# VOLTAGE_SOURCE.net
KiCad netlist of a schematic drawn in Altium Designer
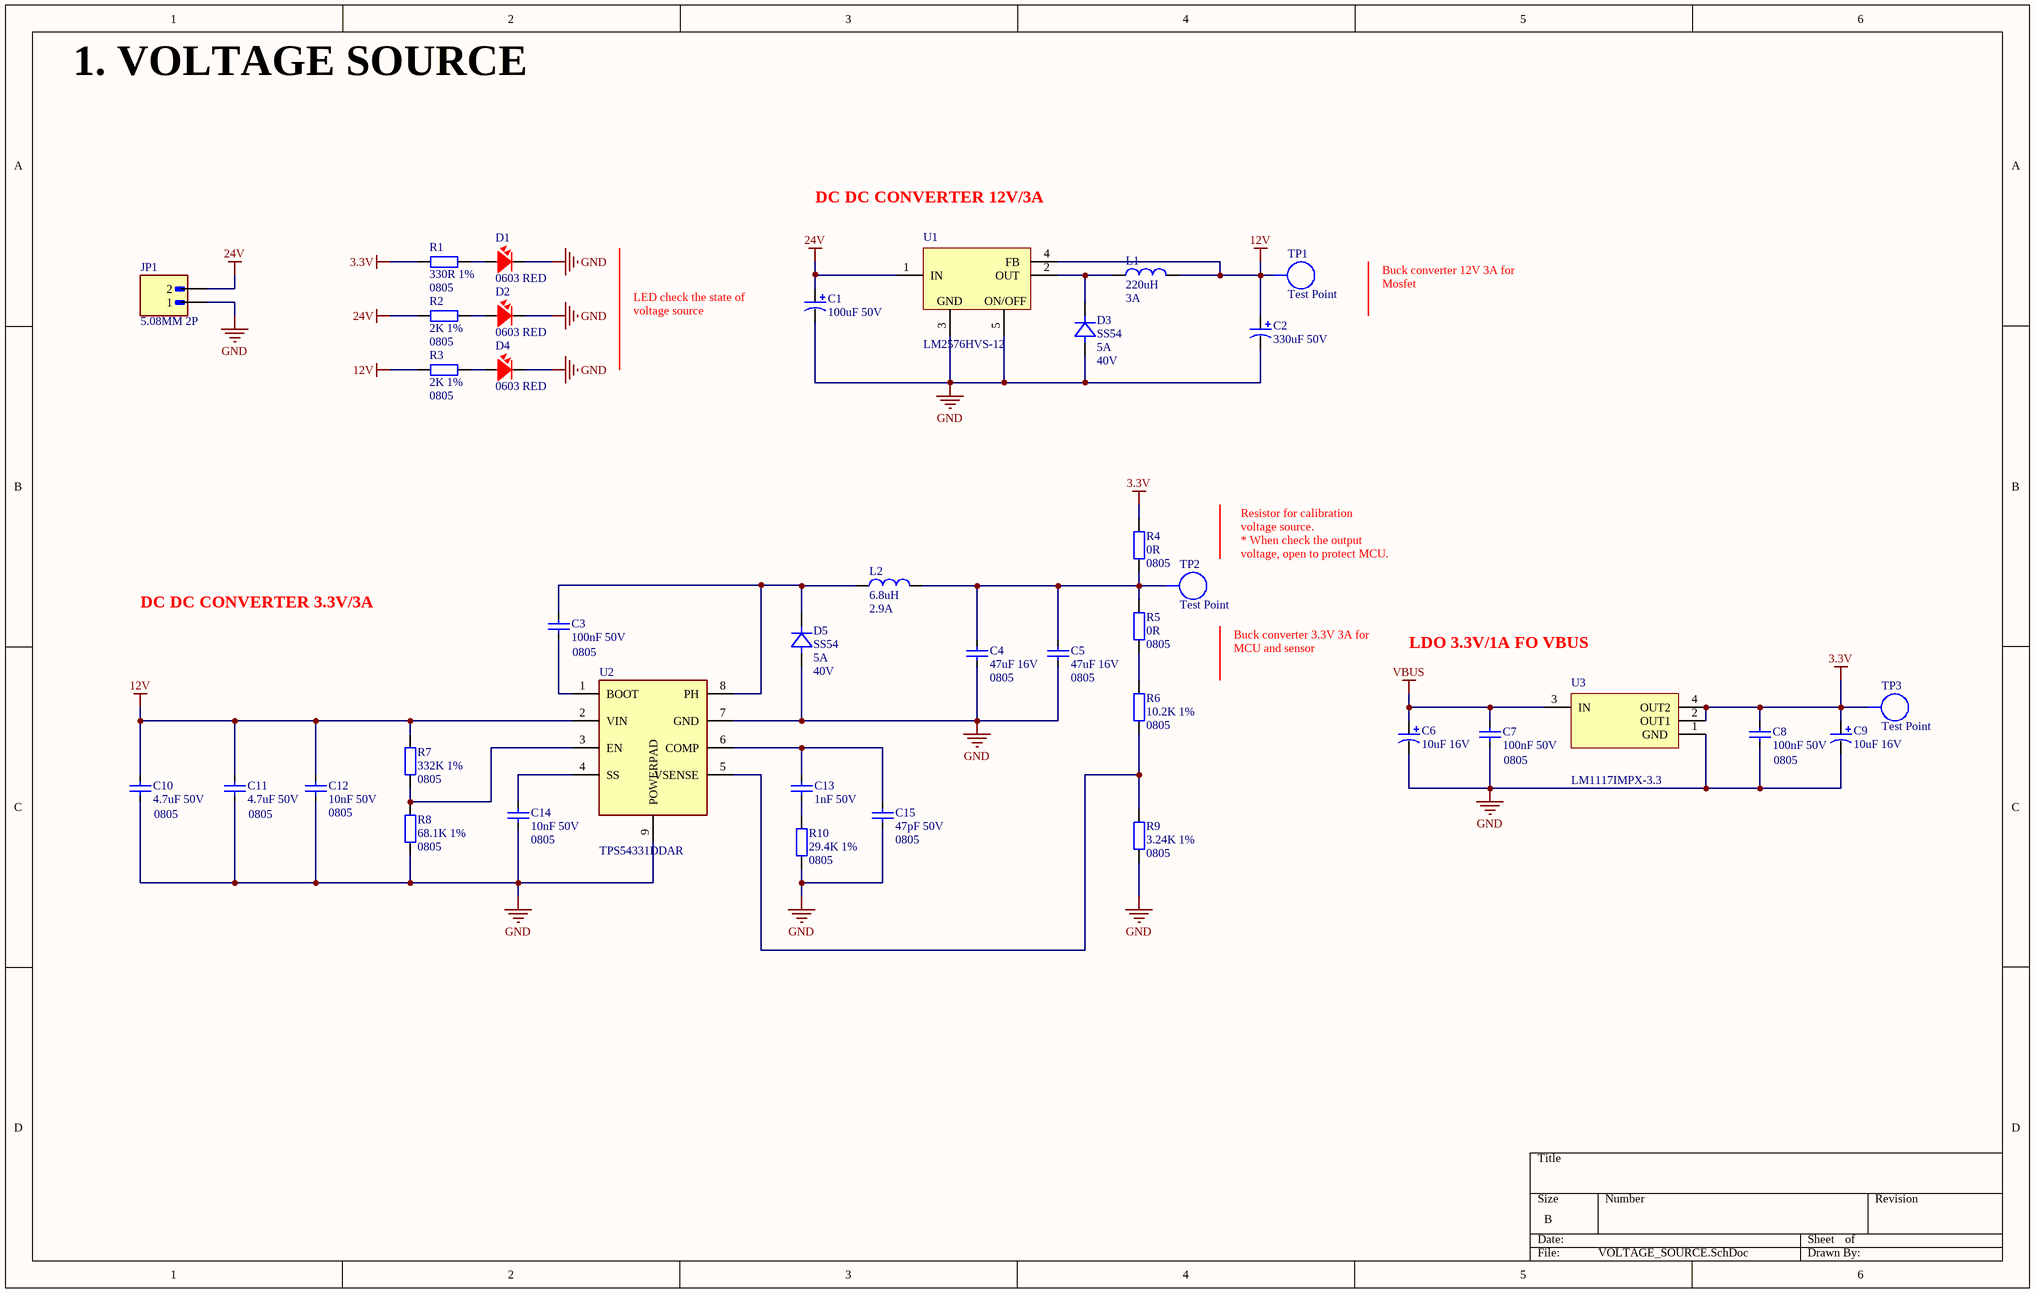
[diagram p0: VOLTAGE_SOURCE.SchDoc]

(export (version "E")
  (design (tool "Eeschema 10.0.6"))
  (components
    (comp (ref "C1")
      (value "100uF 50V")
      (footprint "CAP-ALU-SMD-F-NEW")
      (description "100uF 50V 140mA@120Hz ±20% SMD,D8xL10mm Aluminum Electrolytic Capacitors - SMD ROHS")
      (fields
        (field (name "MANUFACTURER") "Nichicon")
        (field (name "MANUFACTURE PART NUMBER") "UWT1H101MNL1GS")
      )
      (libsource (lib "Capacitors") (part "C_ALU_100uF_50V_F"))
    )
    (comp (ref "C2")
      (value "330uF 50V")
      (footprint "CAP-ALU-SMD-G-NEW")
      (description "330uF 50V 170mA@120Hz ±20% SMD,D10xL10.2mm Aluminum Electrolytic Capacitors - SMD ROHS")
      (fields
        (field (name "MANUFACTURER") "KNSCHA")
        (field (name "MANUFACTURE PART NUMBER") "RVT330UF50V167RV085")
      )
      (libsource (lib "Capacitors") (part "C_ALU_330uF_50V_G"))
    )
    (comp (ref "C3")
      (value "100nF 50V")
      (footprint "CAP_SMD_0805_NEW")
      (description "0.1 µF ±10% 50V Ceramic Capacitor X7R 0805 (2012 Metric)")
      (fields
        (field (name "MANUFACTURER") "YAGEO")
        (field (name "MANUFACTURE PART NUMBER") "CC0805KRX7R9BB104")
        (field (name "SIZE") "0805")
      )
      (libsource (lib "Capacitors") (part "C0805_MLCC_100nF_50V"))
    )
    (comp (ref "C4")
      (value "47uF 16V")
      (footprint "CAP_SMD_0805_NEW")
      (description "47 µF ±10% 16V Ceramic Capacitor X5R 1210 (3225 Metric)")
      (fields
        (field (name "MANUFACTURER") "Samsung Electro-Mechanics")
        (field (name "MANUFACTURE PART NUMBER") "CL32A476KOJNNNE")
        (field (name "SIZE") "0805")
      )
      (libsource (lib "Capacitors") (part "C0805_MLCC_47uF_16V"))
    )
    (comp (ref "C5")
      (value "47uF 16V")
      (footprint "CAP_SMD_0805_NEW")
      (description "47 µF ±10% 16V Ceramic Capacitor X5R 1210 (3225 Metric)")
      (fields
        (field (name "MANUFACTURER") "Samsung Electro-Mechanics")
        (field (name "MANUFACTURE PART NUMBER") "CL32A476KOJNNNE")
        (field (name "SIZE") "0805")
      )
      (libsource (lib "Capacitors") (part "C0805_MLCC_47uF_16V"))
    )
    (comp (ref "C6")
      (value "10uF 16V")
      (footprint "CAP-ALU-SMD-B -NEW")
      (description "10uF 16V 14mA@120Hz ±20% SMD,D4xL5.4mm Aluminum Electrolytic Capacitors - SMD ROHS")
      (fields (field (name "MANUFACTURER") "KNSCHA") (field (name "MANUFACTURE PART NUMBER") "RST10UF16V013"))
      (libsource (lib "Capacitors") (part "C_ALU_10uF_16V_B"))
    )
    (comp (ref "C7")
      (value "100nF 50V")
      (footprint "CAP_SMD_0805_NEW")
      (description "0.1 µF ±10% 50V Ceramic Capacitor X7R 0805 (2012 Metric)")
      (fields
        (field (name "MANUFACTURER") "YAGEO")
        (field (name "MANUFACTURE PART NUMBER") "CC0805KRX7R9BB104")
        (field (name "SIZE") "0805")
      )
      (libsource (lib "Capacitors") (part "C0805_MLCC_100nF_50V"))
    )
    (comp (ref "C8")
      (value "100nF 50V")
      (footprint "CAP_SMD_0805_NEW")
      (description "0.1 µF ±10% 50V Ceramic Capacitor X7R 0805 (2012 Metric)")
      (fields
        (field (name "MANUFACTURER") "YAGEO")
        (field (name "MANUFACTURE PART NUMBER") "CC0805KRX7R9BB104")
        (field (name "SIZE") "0805")
      )
      (libsource (lib "Capacitors") (part "C0805_MLCC_100nF_50V"))
    )
    (comp (ref "C9")
      (value "10uF 16V")
      (footprint "CAP-ALU-SMD-B -NEW")
      (description "10uF 16V 14mA@120Hz ±20% SMD,D4xL5.4mm Aluminum Electrolytic Capacitors - SMD ROHS")
      (fields (field (name "MANUFACTURER") "KNSCHA") (field (name "MANUFACTURE PART NUMBER") "RST10UF16V013"))
      (libsource (lib "Capacitors") (part "C_ALU_10uF_16V_B"))
    )
    (comp (ref "C10")
      (value "4.7uF 50V")
      (footprint "CAP_SMD_0805_NEW")
      (description "4.7 µF ±10% 50V Ceramic Capacitor X5R 0805 (2012 Metric)")
      (fields
        (field (name "MANUFACTURER") "Samsung Electro-Mechanics")
        (field (name "MANUFACTURE PART NUMBER") "CL21A475KBQNNNE")
        (field (name "SIZE") "0805")
      )
      (libsource (lib "Capacitors") (part "C0805_MLCC_4.7uF_50V"))
    )
    (comp (ref "C11")
      (value "4.7uF 50V")
      (footprint "CAP_SMD_0805_NEW")
      (description "4.7 µF ±10% 50V Ceramic Capacitor X5R 0805 (2012 Metric)")
      (fields
        (field (name "MANUFACTURER") "Samsung Electro-Mechanics")
        (field (name "MANUFACTURE PART NUMBER") "CL21A475KBQNNNE")
        (field (name "SIZE") "0805")
      )
      (libsource (lib "Capacitors") (part "C0805_MLCC_4.7uF_50V"))
    )
    (comp (ref "C12")
      (value "10nF 50V")
      (footprint "CAP_SMD_0805_NEW")
      (description "10000 pF ±10% 50V Ceramic Capacitor X7R 0805 (2012 Metric)")
      (fields
        (field (name "MANUFACTURER") "Samsung Electro-Mechanics")
        (field (name "MANUFACTURE PART NUMBER") "CL21B103KBANNNC")
        (field (name "SIZE") "0805")
      )
      (libsource (lib "Capacitors") (part "C0805_MLCC_10nF_50V"))
    )
    (comp (ref "C13")
      (value "1nF 50V")
      (footprint "CAP_SMD_0805_NEW")
      (description "1000 pF ±5% 50V Ceramic Capacitor C0G, NP0 0805 (2012 Metric)")
      (fields
        (field (name "MANUFACTURER") "KEMET")
        (field (name "MANUFACTURE PART NUMBER") "C0805C102J5GAC7800")
      )
      (libsource (lib "Capacitors") (part "C0805_MLCC_1nF_50V"))
    )
    (comp (ref "C14")
      (value "10nF 50V")
      (footprint "CAP_SMD_0805_NEW")
      (description "10000 pF ±10% 50V Ceramic Capacitor X7R 0805 (2012 Metric)")
      (fields
        (field (name "MANUFACTURER") "Samsung Electro-Mechanics")
        (field (name "MANUFACTURE PART NUMBER") "CL21B103KBANNNC")
        (field (name "SIZE") "0805")
      )
      (libsource (lib "Capacitors") (part "C0805_MLCC_10nF_50V"))
    )
    (comp (ref "C15")
      (value "47pF 50V")
      (footprint "CAP_SMD_0805_NEW")
      (description "47 pF ±5% 50V Ceramic Capacitor C0G, NP0 0805 (2012 Metric)")
      (fields
        (field (name "MANUFACTURER") "YAGEO")
        (field (name "MANUFACTURE PART NUMBER") "CC0805JRNPO9BN470")
        (field (name "SIZE") "0805")
      )
      (libsource (lib "Capacitors") (part "C0805_MLCC_47pF_50V"))
    )
    (comp (ref "D1")
      (value "0603 RED")
      (footprint "LED-0603")
      (description "Red 625nm LED Indication - Discrete 2V 0603 (1608 Metric)")
      (fields
        (field (name "MANUFACTURER") "Würth Elektronik")
        (field (name "MANUFACTURE PART NUMBER") "150060RS75000")
      )
      (libsource (lib "LEDs") (part "LED_0603_RED"))
    )
    (comp (ref "D2")
      (value "0603 RED")
      (footprint "LED-0603")
      (description "Red 625nm LED Indication - Discrete 2V 0603 (1608 Metric)")
      (fields
        (field (name "MANUFACTURER") "Würth Elektronik")
        (field (name "MANUFACTURE PART NUMBER") "150060RS75000")
      )
      (libsource (lib "LEDs") (part "LED_0603_RED"))
    )
    (comp (ref "D3")
      (value "SS54")
      (footprint "SMA")
      (description "DIODE SCHOTTKY 40V 5A SMA")
      (fields
        (field (name "MANUFACTURER") "EVVO")
        (field (name "CURRENT") "5A")
        (field (name "DC VOLTAGE") "40V")
      )
      (libsource (lib "Diode") (part "SS54"))
    )
    (comp (ref "D4")
      (value "0603 RED")
      (footprint "LED-0603")
      (description "Red 625nm LED Indication - Discrete 2V 0603 (1608 Metric)")
      (fields
        (field (name "MANUFACTURER") "Würth Elektronik")
        (field (name "MANUFACTURE PART NUMBER") "150060RS75000")
      )
      (libsource (lib "LEDs") (part "LED_0603_RED"))
    )
    (comp (ref "D5")
      (value "SS54")
      (footprint "SMA")
      (description "DIODE SCHOTTKY 40V 5A SMA")
      (fields
        (field (name "MANUFACTURER") "EVVO")
        (field (name "CURRENT") "5A")
        (field (name "DC VOLTAGE") "40V")
      )
      (libsource (lib "Diode") (part "SS54"))
    )
    (comp (ref "JP1")
      (value "5.08MM 2P")
      (footprint "5.08MM 2P")
      (fields
        (field (name "MANUFACTURER") "Phoenix Contact")
        (field (name "MANUFACTURE PART NUMBER") "1759017")
      )
      (libsource (lib "Connectors") (part "TERMINAL_5.08MM_2P"))
    )
    (comp (ref "L1")
      (value "220uH 3A")
      (footprint "L_TOR_13x7")
      (fields (field (name "INDUCTOR") "220uH") (field (name "CURRENT") "3A"))
      (libsource (lib "Inductors") (part "L_220uH_3A_LM2576"))
    )
    (comp (ref "L2")
      (value "CD74R_6.8uH")
      (footprint "CD74R")
      (description "2.9A 6.8uH ±30% SMD,7.5x7.5mm Power Inductors ROHS")
      (fields
        (field (name "MANUFACTURER") "SHOU HAN")
        (field (name "MANUFACTURE PART NUMBER") "CYH74-6.8UH")
        (field (name "INDUCTOR") "6.8uH")
        (field (name "CURRENT") "2.9A")
      )
      (libsource (lib "Inductors") (part "CD74R_6.8uH"))
    )
    (comp (ref "R1")
      (value "330R 1%")
      (footprint "RES_SMD_0805")
      (description "330 Ohms ±1% 0.125W, 1/8W Chip Resistor 0805 (2012 Metric) Automotive AEC-Q200 Thick Film")
      (fields
        (field (name "MANUFACTURER") "Stackpole Electronics Inc")
        (field (name "MANUFACTURE PART NUMBER") "RMCF0805FT330R")
        (field (name "SIZE") "0805")
      )
      (libsource (lib "Resistors") (part "R0805_330R"))
    )
    (comp (ref "R2")
      (value "2K 1%")
      (footprint "RES_SMD_0805")
      (description "2 kOhms ±1% 0.125W, 1/8W Chip Resistor 0805 (2012 Metric) Automotive AEC-Q200 Thick Film")
      (fields
        (field (name "MANUFACTURER") "Panasonic Electronic Components")
        (field (name "MANUFACTURE PART NUMBER") "ERJ-6ENF2001V")
        (field (name "SIZE") "0805")
      )
      (libsource (lib "Resistors") (part "R0805_2K"))
    )
    (comp (ref "R3")
      (value "2K 1%")
      (footprint "RES_SMD_0805")
      (description "2 kOhms ±1% 0.125W, 1/8W Chip Resistor 0805 (2012 Metric) Automotive AEC-Q200 Thick Film")
      (fields
        (field (name "MANUFACTURER") "Panasonic Electronic Components")
        (field (name "MANUFACTURE PART NUMBER") "ERJ-6ENF2001V")
        (field (name "SIZE") "0805")
      )
      (libsource (lib "Resistors") (part "R0805_2K"))
    )
    (comp (ref "R4")
      (value "0R")
      (footprint "RES_SMD_0805")
      (description "0 Ohms Jumper Chip Resistor 0805 (2012 Metric) Automotive AEC-Q200 Thick Film")
      (fields
        (field (name "MANUFACTURER") "Vishay Dale")
        (field (name "MANUFACTURE PART NUMBER") "CRCW08050000Z0EA")
        (field (name "SIZE") "0805")
      )
      (libsource (lib "Resistors") (part "R0805_0R"))
    )
    (comp (ref "R5")
      (value "0R")
      (footprint "RES_SMD_0805")
      (description "0 Ohms Jumper Chip Resistor 0805 (2012 Metric) Automotive AEC-Q200 Thick Film")
      (fields
        (field (name "MANUFACTURER") "Vishay Dale")
        (field (name "MANUFACTURE PART NUMBER") "CRCW08050000Z0EA")
        (field (name "SIZE") "0805")
      )
      (libsource (lib "Resistors") (part "R0805_0R"))
    )
    (comp (ref "R6")
      (value "10.2K 1%")
      (footprint "RES_SMD_0805")
      (description "10.2 kOhms ±1% 0.125W, 1/8W Chip Resistor 0805 (2012 Metric) Moisture Resistant Thick Film")
      (fields
        (field (name "MANUFACTURER") "YAGEO")
        (field (name "MANUFACTURE PART NUMBER") "RC0805FR-0710K2L")
        (field (name "SIZE") "0805")
      )
      (libsource (lib "Resistors") (part "R0805_10.2K"))
    )
    (comp (ref "R7")
      (value "332K 1%")
      (footprint "RES_SMD_0805")
      (description "332 kOhms ±1% 0.125W, 1/8W Chip Resistor 0805 (2012 Metric) Moisture Resistant Thick Film")
      (fields
        (field (name "MANUFACTURER") "YAGEO")
        (field (name "MANUFACTURE PART NUMBER") "RC0805FR-07332KL")
        (field (name "SIZE") "0805")
      )
      (libsource (lib "Resistors") (part "R0805_332K"))
    )
    (comp (ref "R8")
      (value "68.1K 1%")
      (footprint "RES_SMD_0805")
      (description "68.1 kOhms ±1% 0.125W, 1/8W Chip Resistor 0805 (2012 Metric) Moisture Resistant Thick Film")
      (fields
        (field (name "MANUFACTURER") "YAGEO")
        (field (name "MANUFACTURE PART NUMBER") "RC0805FR-0768K1L")
        (field (name "SIZE") "0805")
      )
      (libsource (lib "Resistors") (part "R0805_68.1K"))
    )
    (comp (ref "R9")
      (value "3.24K 1%")
      (footprint "RES_SMD_0805")
      (description "3.24 kOhms ±1% 0.125W, 1/8W Chip Resistor 0805 (2012 Metric) Moisture Resistant Thick Film")
      (fields
        (field (name "MANUFACTURER") "YAGEO")
        (field (name "MANUFACTURE PART NUMBER") "RC0805FR-073K24L")
        (field (name "SIZE") "0805")
      )
      (libsource (lib "Resistors") (part "R0805_3.24K"))
    )
    (comp (ref "R10")
      (value "29.4K 1%")
      (footprint "RES_SMD_0805")
      (description "29.4 kOhms ±1% 0.125W, 1/8W Chip Resistor 0805 (2012 Metric) Moisture Resistant Thick Film")
      (fields
        (field (name "MANUFACTURER") "YAGEO")
        (field (name "MANUFACTURE PART NUMBER") "RC0805FR-0729K4L")
        (field (name "SIZE") "0805")
      )
      (libsource (lib "Resistors") (part "R0805_29.4K"))
    )
    (comp (ref "TP1")
      (value "Test Point")
      (footprint "TEST_POINT")
      (libsource (lib "Connectors") (part "TEST_POINT"))
    )
    (comp (ref "TP2")
      (value "Test Point")
      (footprint "TEST_POINT")
      (libsource (lib "Connectors") (part "TEST_POINT"))
    )
    (comp (ref "TP3")
      (value "Test Point")
      (footprint "TEST_POINT")
      (libsource (lib "Connectors") (part "TEST_POINT"))
    )
    (comp (ref "U1")
      (value "LM2576HVS-12")
      (footprint "IC_LM2596SX-12/NOPB")
      (fields (field (name "MANUFACTURER") "Texas Instruments"))
      (libsource (lib "Voltage_Regulators") (part "LM2576HVS-12"))
    )
    (comp (ref "U2")
      (value "TPS54331DDAR")
      (footprint "TPS54531DDAR")
      (fields (field (name "MANUFACTURER") "Texas Instruments"))
      (libsource (lib "Voltage_Regulators") (part "TPS54331DDAR"))
    )
    (comp (ref "U3")
      (value "LM1117IMPX-3.3")
      (footprint "SOT-223-4")
      (description "Linear Voltage Regulator IC Positive Fixed 1 Output 800mA SOT-223-4")
      (fields
        (field (name "MANUFACTURER") "Texas Instruments")
        (field (name "MANUFACTURE PART NUMBER") "LM1117IMPX-3.3/NOPB")
      )
      (libsource (lib "Voltage_Regulators") (part "LM1117IMPX-3.3/NOPB"))
    )
  )
  (nets
    (net (code "1") (name "3.3V") (class "Default")
      (node (ref "C8") (pin "2") (pinfunction "2_2") (pintype "passive"))
      (node (ref "C9") (pin "1") (pinfunction "1_1") (pintype "passive"))
      (node (ref "R1") (pin "1") (pinfunction "1_1") (pintype "passive"))
      (node (ref "R4") (pin "2") (pinfunction "2_2") (pintype "passive"))
      (node (ref "TP3") (pin "1") (pinfunction "1_1") (pintype "passive"))
      (node (ref "U3") (pin "2") (pinfunction "OUT1_2") (pintype "passive"))
      (node (ref "U3") (pin "4") (pinfunction "OUT2_4") (pintype "passive"))
    )
    (net (code "2") (name "12V") (class "Default")
      (node (ref "C10") (pin "2") (pinfunction "2_2") (pintype "passive"))
      (node (ref "C11") (pin "2") (pinfunction "2_2") (pintype "passive"))
      (node (ref "C12") (pin "2") (pinfunction "2_2") (pintype "passive"))
      (node (ref "C2") (pin "1") (pinfunction "1_1") (pintype "passive"))
      (node (ref "L1") (pin "2") (pinfunction "2_2") (pintype "passive"))
      (node (ref "R3") (pin "2") (pinfunction "2_2") (pintype "passive"))
      (node (ref "R7") (pin "2") (pinfunction "2_2") (pintype "passive"))
      (node (ref "TP1") (pin "1") (pinfunction "1_1") (pintype "passive"))
      (node (ref "U1") (pin "4") (pinfunction "FB_4") (pintype "passive"))
      (node (ref "U2") (pin "2") (pinfunction "VIN_2") (pintype "passive"))
    )
    (net (code "3") (name "24V") (class "Default")
      (node (ref "C1") (pin "1") (pinfunction "1_1") (pintype "passive"))
      (node (ref "JP1") (pin "2") (pinfunction "2_2") (pintype "passive"))
      (node (ref "R2") (pin "2") (pinfunction "2_2") (pintype "passive"))
      (node (ref "U1") (pin "1") (pinfunction "IN_1") (pintype "passive"))
    )
    (net (code "4") (name "GND") (class "Default")
      (node (ref "C1") (pin "2") (pinfunction "2_2") (pintype "passive"))
      (node (ref "C10") (pin "1") (pinfunction "1_1") (pintype "passive"))
      (node (ref "C11") (pin "1") (pinfunction "1_1") (pintype "passive"))
      (node (ref "C12") (pin "1") (pinfunction "1_1") (pintype "passive"))
      (node (ref "C14") (pin "1") (pinfunction "1_1") (pintype "passive"))
      (node (ref "C15") (pin "1") (pinfunction "1_1") (pintype "passive"))
      (node (ref "C2") (pin "2") (pinfunction "2_2") (pintype "passive"))
      (node (ref "C4") (pin "1") (pinfunction "1_1") (pintype "passive"))
      (node (ref "C5") (pin "1") (pinfunction "1_1") (pintype "passive"))
      (node (ref "C6") (pin "2") (pinfunction "2_2") (pintype "passive"))
      (node (ref "C7") (pin "1") (pinfunction "1_1") (pintype "passive"))
      (node (ref "C8") (pin "1") (pinfunction "1_1") (pintype "passive"))
      (node (ref "C9") (pin "2") (pinfunction "2_2") (pintype "passive"))
      (node (ref "D1") (pin "2") (pinfunction "2_2") (pintype "passive"))
      (node (ref "D2") (pin "2") (pinfunction "2_2") (pintype "passive"))
      (node (ref "D3") (pin "A") (pinfunction "A_A") (pintype "passive"))
      (node (ref "D4") (pin "2") (pinfunction "2_2") (pintype "passive"))
      (node (ref "D5") (pin "A") (pinfunction "A_A") (pintype "passive"))
      (node (ref "JP1") (pin "1") (pinfunction "1_1") (pintype "passive"))
      (node (ref "R10") (pin "1") (pinfunction "1_1") (pintype "passive"))
      (node (ref "R8") (pin "1") (pinfunction "1_1") (pintype "passive"))
      (node (ref "R9") (pin "1") (pinfunction "1_1") (pintype "passive"))
      (node (ref "U1") (pin "3") (pinfunction "GND_3") (pintype "passive"))
      (node (ref "U1") (pin "5") (pinfunction "ON/OFF_5") (pintype "passive"))
      (node (ref "U2") (pin "7") (pinfunction "GND_7") (pintype "passive"))
      (node (ref "U2") (pin "9") (pinfunction "POWERPAD_9") (pintype "passive"))
      (node (ref "U3") (pin "1") (pinfunction "GND_1") (pintype "passive"))
    )
    (net (code "5") (name "Net-(C4-Pad2)") (class "Default")
      (node (ref "C4") (pin "2") (pinfunction "2_2") (pintype "passive"))
      (node (ref "C5") (pin "2") (pinfunction "2_2") (pintype "passive"))
      (node (ref "L2") (pin "2") (pinfunction "2_2") (pintype "passive"))
      (node (ref "R4") (pin "1") (pinfunction "1_1") (pintype "passive"))
      (node (ref "R5") (pin "2") (pinfunction "2_2") (pintype "passive"))
      (node (ref "TP2") (pin "1") (pinfunction "1_1") (pintype "passive"))
    )
    (net (code "6") (name "Net-(C13-Pad1)") (class "Default")
      (node (ref "C13") (pin "1") (pinfunction "1_1") (pintype "passive"))
      (node (ref "R10") (pin "2") (pinfunction "2_2") (pintype "passive"))
    )
    (net (code "7") (name "Net-(D1-Pad1)") (class "Default")
      (node (ref "D1") (pin "1") (pinfunction "1_1") (pintype "passive"))
      (node (ref "R1") (pin "2") (pinfunction "2_2") (pintype "passive"))
    )
    (net (code "8") (name "Net-(D2-Pad1)") (class "Default")
      (node (ref "D2") (pin "1") (pinfunction "1_1") (pintype "passive"))
      (node (ref "R2") (pin "1") (pinfunction "1_1") (pintype "passive"))
    )
    (net (code "9") (name "Net-(D4-Pad1)") (class "Default")
      (node (ref "D4") (pin "1") (pinfunction "1_1") (pintype "passive"))
      (node (ref "R3") (pin "1") (pinfunction "1_1") (pintype "passive"))
    )
    (net (code "10") (name "Net-(R5-Pad1)") (class "Default")
      (node (ref "R5") (pin "1") (pinfunction "1_1") (pintype "passive"))
      (node (ref "R6") (pin "2") (pinfunction "2_2") (pintype "passive"))
    )
    (net (code "11") (name "Net-(U1-OUT)") (class "Default")
      (node (ref "D3") (pin "C") (pinfunction "C_C") (pintype "passive"))
      (node (ref "L1") (pin "1") (pinfunction "1_1") (pintype "passive"))
      (node (ref "U1") (pin "2") (pinfunction "OUT_2") (pintype "passive"))
    )
    (net (code "12") (name "Net-(U2-BOOT)") (class "Default")
      (node (ref "C3") (pin "1") (pinfunction "1_1") (pintype "passive"))
      (node (ref "U2") (pin "1") (pinfunction "BOOT_1") (pintype "passive"))
    )
    (net (code "13") (name "Net-(U2-COMP)") (class "Default")
      (node (ref "C13") (pin "2") (pinfunction "2_2") (pintype "passive"))
      (node (ref "C15") (pin "2") (pinfunction "2_2") (pintype "passive"))
      (node (ref "U2") (pin "6") (pinfunction "COMP_6") (pintype "passive"))
    )
    (net (code "14") (name "Net-(U2-EN)") (class "Default")
      (node (ref "R7") (pin "1") (pinfunction "1_1") (pintype "passive"))
      (node (ref "R8") (pin "2") (pinfunction "2_2") (pintype "passive"))
      (node (ref "U2") (pin "3") (pinfunction "EN_3") (pintype "passive"))
    )
    (net (code "15") (name "Net-(U2-PH)") (class "Default")
      (node (ref "C3") (pin "2") (pinfunction "2_2") (pintype "passive"))
      (node (ref "D5") (pin "C") (pinfunction "C_C") (pintype "passive"))
      (node (ref "L2") (pin "1") (pinfunction "1_1") (pintype "passive"))
      (node (ref "U2") (pin "8") (pinfunction "PH_8") (pintype "passive"))
    )
    (net (code "16") (name "Net-(U2-SS)") (class "Default")
      (node (ref "C14") (pin "2") (pinfunction "2_2") (pintype "passive"))
      (node (ref "U2") (pin "4") (pinfunction "SS_4") (pintype "passive"))
    )
    (net (code "17") (name "Net-(U2-VSENSE)") (class "Default")
      (node (ref "R6") (pin "1") (pinfunction "1_1") (pintype "passive"))
      (node (ref "R9") (pin "2") (pinfunction "2_2") (pintype "passive"))
      (node (ref "U2") (pin "5") (pinfunction "VSENSE_5") (pintype "passive"))
    )
    (net (code "18") (name "VBUS") (class "Default")
      (node (ref "C6") (pin "1") (pinfunction "1_1") (pintype "passive"))
      (node (ref "C7") (pin "2") (pinfunction "2_2") (pintype "passive"))
      (node (ref "U3") (pin "3") (pinfunction "IN_3") (pintype "passive"))
    )
  )
)
